# XHDZ-FZ-2E.net
KiCad netlist of a schematic drawn in EAGLE
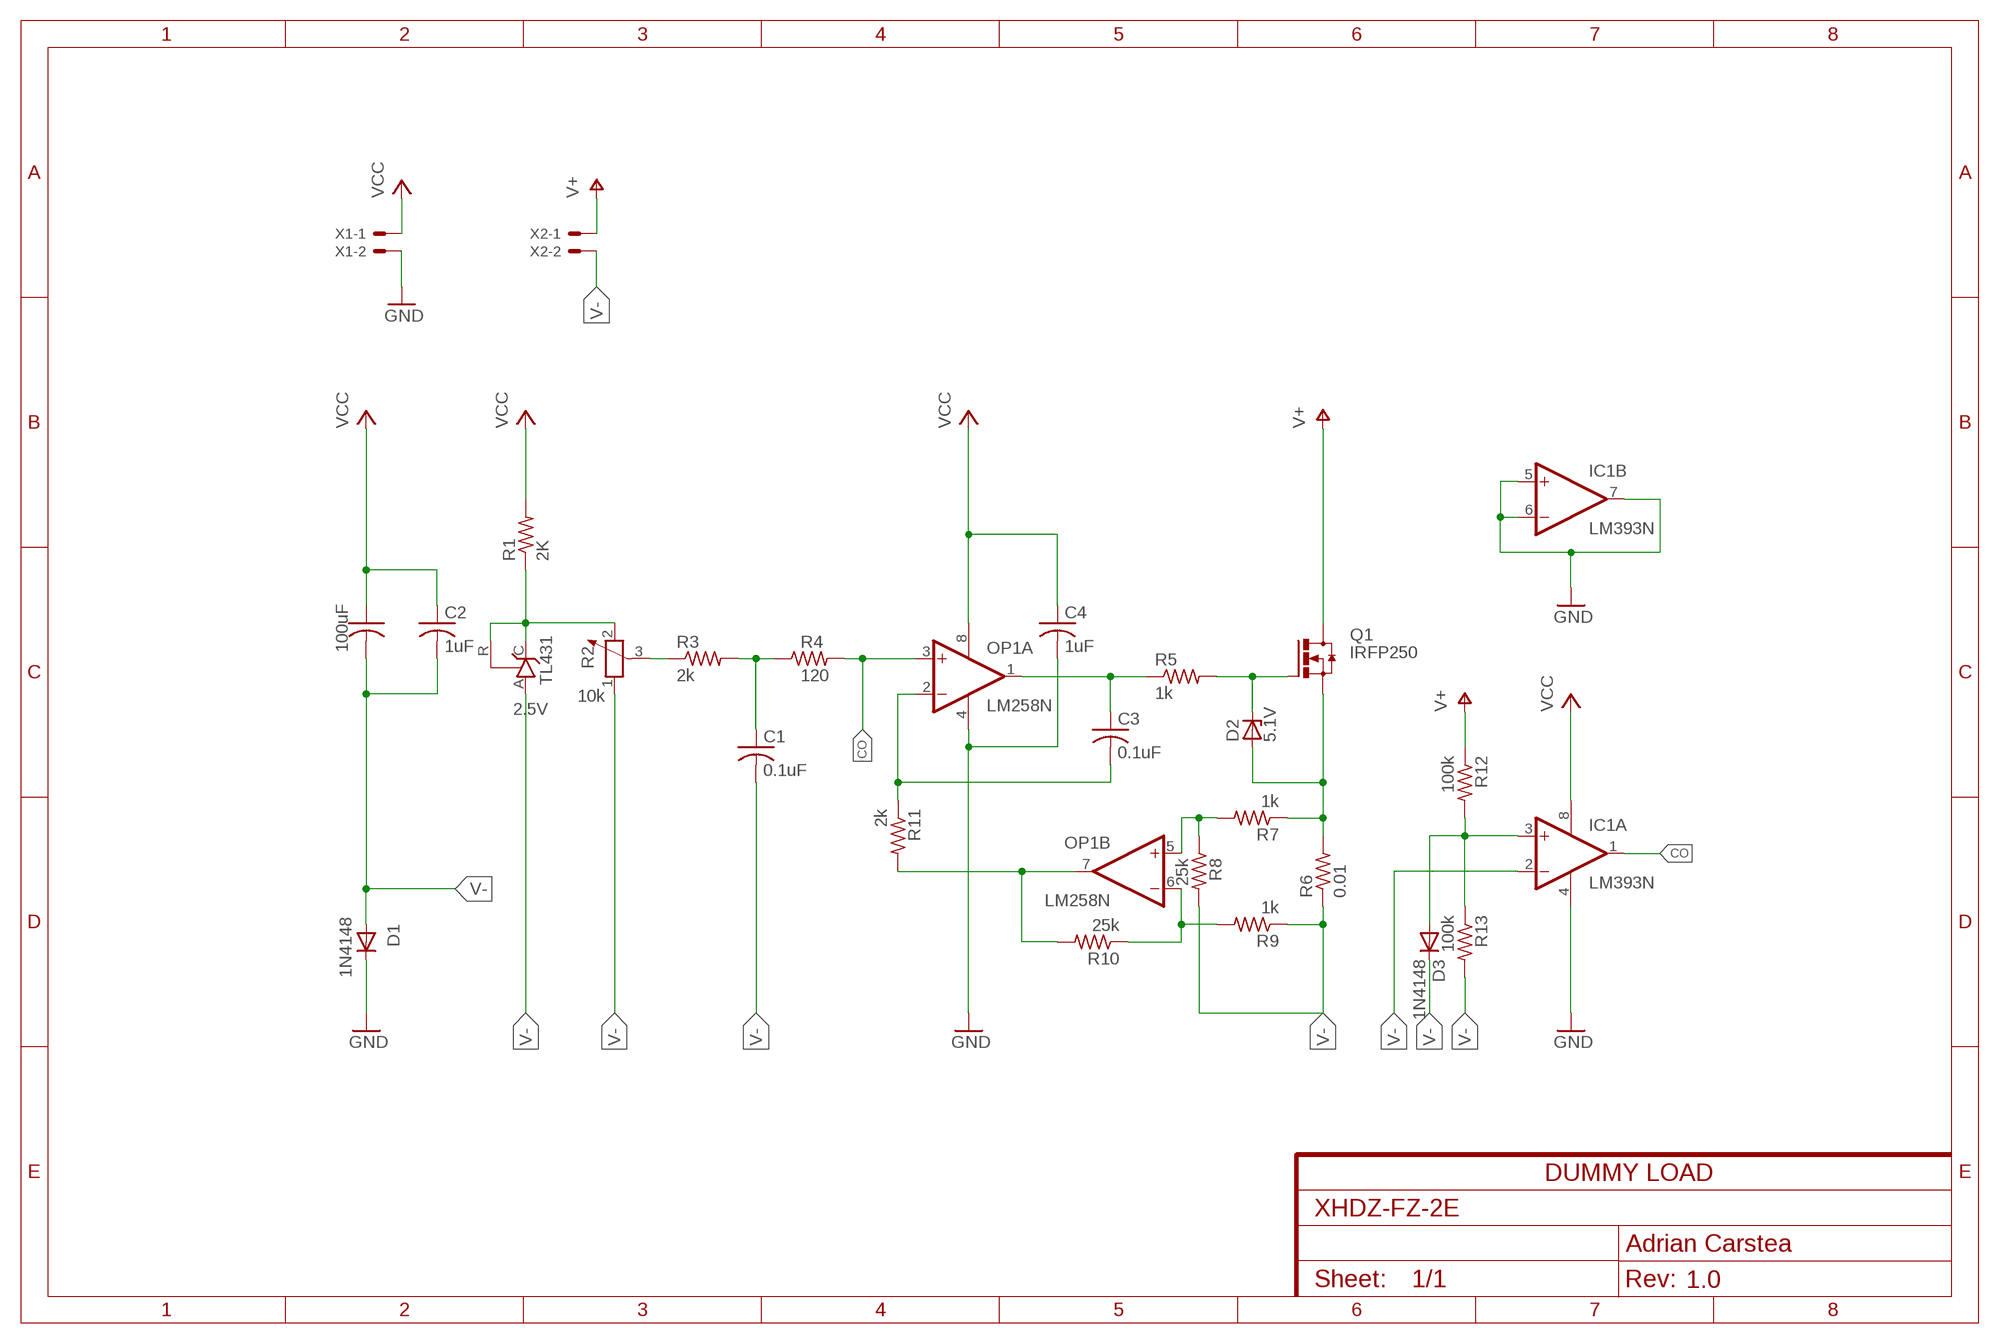
[diagram p0: schematic, sheet 1]

(export (version "E")
  (design (tool "Eeschema 10.0.6"))
  (components
    (comp (ref "25V")
      (value "100uF")
      (footprint "eagle-import:C025-024X044")
      (libsource (lib "eagle-import") (part "C-US025-024X044"))
    )
    (comp (ref "C1")
      (value "0.1uF")
      (footprint "eagle-import:C025-024X044")
      (libsource (lib "eagle-import") (part "C-US025-024X044"))
    )
    (comp (ref "C2")
      (value "1uF")
      (footprint "eagle-import:C025-024X044")
      (libsource (lib "eagle-import") (part "C-US025-024X044"))
    )
    (comp (ref "C3")
      (value "0.1uF")
      (footprint "eagle-import:C025-024X044")
      (libsource (lib "eagle-import") (part "C-US025-024X044"))
    )
    (comp (ref "C4")
      (value "1uF")
      (footprint "eagle-import:C025-024X044")
      (libsource (lib "eagle-import") (part "C-US025-024X044"))
    )
    (comp (ref "D1")
      (value "1N4148")
      (footprint "eagle-import:DO35-7")
      (libsource (lib "eagle-import") (part "1N4148DO35-7"))
    )
    (comp (ref "D2")
      (value "5.1V")
      (footprint "eagle-import:C1702-15")
      (libsource (lib "eagle-import") (part "ZENER-DIODEC1702-15"))
    )
    (comp (ref "D3")
      (value "1N4148")
      (footprint "eagle-import:DO35-7")
      (libsource (lib "eagle-import") (part "1N4148DO35-7"))
    )
    (comp (ref "IC1")
      (value "LM393N")
      (footprint "eagle-import:DIL08")
      (libsource (lib "eagle-import") (part "LM393N"))
    )
    (comp (ref "OP1")
      (value "LM258N")
      (footprint "eagle-import:DIL08")
      (libsource (lib "eagle-import") (part "LM358N"))
    )
    (comp (ref "Q1")
      (value "IRFP250")
      (footprint "eagle-import:TO-247AD-V")
      (libsource (lib "eagle-import") (part "IRFP250"))
    )
    (comp (ref "R1")
      (value "2K")
      (footprint "eagle-import:0207_5V")
      (libsource (lib "eagle-import") (part "R-US_0207/5V"))
    )
    (comp (ref "R2")
      (value "10k")
      (footprint "eagle-import:PT-10")
      (libsource (lib "eagle-import") (part "POTENTIOMETER_PT-10"))
    )
    (comp (ref "R3")
      (value "2k")
      (footprint "eagle-import:0207_5V")
      (libsource (lib "eagle-import") (part "R-US_0207/5V"))
    )
    (comp (ref "R4")
      (value "120")
      (footprint "eagle-import:0207_5V")
      (libsource (lib "eagle-import") (part "R-US_0207/5V"))
    )
    (comp (ref "R5")
      (value "1k")
      (footprint "eagle-import:0207_5V")
      (libsource (lib "eagle-import") (part "R-US_0207/5V"))
    )
    (comp (ref "R6")
      (value "0.01")
      (footprint "eagle-import:0207_5V")
      (libsource (lib "eagle-import") (part "R-US_0207/5V"))
    )
    (comp (ref "R7")
      (value "1k")
      (footprint "eagle-import:0207_5V")
      (libsource (lib "eagle-import") (part "R-US_0207/5V"))
    )
    (comp (ref "R8")
      (value "25k")
      (footprint "eagle-import:0207_5V")
      (libsource (lib "eagle-import") (part "R-US_0207/5V"))
    )
    (comp (ref "R9")
      (value "1k")
      (footprint "eagle-import:0207_5V")
      (libsource (lib "eagle-import") (part "R-US_0207/5V"))
    )
    (comp (ref "R10")
      (value "25k")
      (footprint "eagle-import:0207_5V")
      (libsource (lib "eagle-import") (part "R-US_0207/5V"))
    )
    (comp (ref "R11")
      (value "2k")
      (footprint "eagle-import:0207_5V")
      (libsource (lib "eagle-import") (part "R-US_0207/5V"))
    )
    (comp (ref "R12")
      (value "100k")
      (footprint "eagle-import:0207_5V")
      (libsource (lib "eagle-import") (part "R-US_0207/5V"))
    )
    (comp (ref "R13")
      (value "100k")
      (footprint "eagle-import:0207_5V")
      (libsource (lib "eagle-import") (part "R-US_0207/5V"))
    )
    (comp (ref "TL431")
      (value "2.5V")
      (footprint "eagle-import:TO92-CLP")
      (libsource (lib "eagle-import") (part "TL431CLP"))
    )
    (comp (ref "X1")
      (value "22-23-2021")
      (footprint "eagle-import:22-23-2021")
      (fields (field (name "MF") "MOLEX"))
      (libsource (lib "eagle-import") (part "22-23-2021"))
    )
    (comp (ref "X2")
      (value "22-23-2021")
      (footprint "eagle-import:22-23-2021")
      (fields (field (name "MF") "MOLEX"))
      (libsource (lib "eagle-import") (part "22-23-2021"))
    )
  )
  (nets
    (net (code "1") (name "CO") (class "Default")
      (node (ref "IC1") (pin "1") (pinfunction "OUT_1") (pintype "output"))
      (node (ref "OP1") (pin "3") (pinfunction "+IN_3") (pintype "input"))
      (node (ref "R4") (pin "2") (pinfunction "2_2") (pintype "passive"))
    )
    (net (code "2") (name "GND") (class "Default")
      (node (ref "C4") (pin "2") (pinfunction "2_2") (pintype "passive"))
      (node (ref "D1") (pin "C") (pinfunction "C_C") (pintype "passive"))
      (node (ref "IC1") (pin "4") (pinfunction "V-_4") (pintype "power_in"))
      (node (ref "IC1") (pin "5") (pinfunction "+IN_5") (pintype "input"))
      (node (ref "IC1") (pin "6") (pinfunction "-IN_6") (pintype "input"))
      (node (ref "IC1") (pin "7") (pinfunction "OUT_7") (pintype "output"))
      (node (ref "OP1") (pin "4") (pinfunction "V-_4") (pintype "power_in"))
      (node (ref "X1") (pin "2") (pinfunction "S_2") (pintype "passive"))
    )
    (net (code "3") (name "Net-(C1-Pad1)") (class "Default")
      (node (ref "C1") (pin "1") (pinfunction "1_1") (pintype "passive"))
      (node (ref "R3") (pin "2") (pinfunction "2_2") (pintype "passive"))
      (node (ref "R4") (pin "1") (pinfunction "1_1") (pintype "passive"))
    )
    (net (code "4") (name "Net-(D2-PadA)") (class "Default")
      (node (ref "D2") (pin "A") (pinfunction "A_A") (pintype "passive"))
      (node (ref "Q1") (pin "S") (pinfunction "S_S") (pintype "passive"))
      (node (ref "R6") (pin "2") (pinfunction "2_2") (pintype "passive"))
      (node (ref "R7") (pin "1") (pinfunction "1_1") (pintype "passive"))
    )
    (net (code "5") (name "Net-(D2-PadC)") (class "Default")
      (node (ref "D2") (pin "C") (pinfunction "C_C") (pintype "passive"))
      (node (ref "Q1") (pin "G") (pinfunction "G_G") (pintype "passive"))
      (node (ref "R5") (pin "2") (pinfunction "2_2") (pintype "passive"))
    )
    (net (code "6") (name "Net-(IC1A-+IN)") (class "Default")
      (node (ref "D3") (pin "A") (pinfunction "A_A") (pintype "passive"))
      (node (ref "IC1") (pin "3") (pinfunction "+IN_3") (pintype "input"))
      (node (ref "R12") (pin "2") (pinfunction "2_2") (pintype "passive"))
      (node (ref "R13") (pin "1") (pinfunction "1_1") (pintype "passive"))
    )
    (net (code "7") (name "Net-(OP1A--IN)") (class "Default")
      (node (ref "C3") (pin "2") (pinfunction "2_2") (pintype "passive"))
      (node (ref "OP1") (pin "2") (pinfunction "-IN_2") (pintype "input"))
      (node (ref "R11") (pin "1") (pinfunction "1_1") (pintype "passive"))
    )
    (net (code "8") (name "Net-(OP1A-OUT)") (class "Default")
      (node (ref "C3") (pin "1") (pinfunction "1_1") (pintype "passive"))
      (node (ref "OP1") (pin "1") (pinfunction "OUT_1") (pintype "output"))
      (node (ref "R5") (pin "1") (pinfunction "1_1") (pintype "passive"))
    )
    (net (code "9") (name "Net-(OP1B-+IN)") (class "Default")
      (node (ref "OP1") (pin "5") (pinfunction "+IN_5") (pintype "input"))
      (node (ref "R7") (pin "2") (pinfunction "2_2") (pintype "passive"))
      (node (ref "R8") (pin "1") (pinfunction "1_1") (pintype "passive"))
    )
    (net (code "10") (name "Net-(OP1B--IN)") (class "Default")
      (node (ref "OP1") (pin "6") (pinfunction "-IN_6") (pintype "input"))
      (node (ref "R10") (pin "1") (pinfunction "1_1") (pintype "passive"))
      (node (ref "R9") (pin "2") (pinfunction "2_2") (pintype "passive"))
    )
    (net (code "11") (name "Net-(OP1B-OUT)") (class "Default")
      (node (ref "OP1") (pin "7") (pinfunction "OUT_7") (pintype "output"))
      (node (ref "R10") (pin "2") (pinfunction "2_2") (pintype "passive"))
      (node (ref "R11") (pin "2") (pinfunction "2_2") (pintype "passive"))
    )
    (net (code "12") (name "Net-(R1-Pad1)") (class "Default")
      (node (ref "R1") (pin "1") (pinfunction "1_1") (pintype "passive"))
      (node (ref "R2") (pin "2") (pinfunction "2_2") (pintype "passive"))
      (node (ref "TL431") (pin "C") (pinfunction "C_C") (pintype "passive"))
      (node (ref "TL431") (pin "R") (pinfunction "R_R") (pintype "passive"))
    )
    (net (code "13") (name "Net-(R2-Pad3)") (class "Default")
      (node (ref "R2") (pin "3") (pinfunction "3_3") (pintype "passive"))
      (node (ref "R3") (pin "1") (pinfunction "1_1") (pintype "passive"))
    )
    (net (code "14") (name "V+") (class "Default")
      (node (ref "Q1") (pin "D") (pinfunction "D_D") (pintype "passive"))
      (node (ref "R12") (pin "1") (pinfunction "1_1") (pintype "passive"))
      (node (ref "X2") (pin "1") (pinfunction "S_1") (pintype "passive"))
    )
    (net (code "15") (name "V-") (class "Default")
      (node (ref "25V") (pin "2") (pinfunction "2_2") (pintype "passive"))
      (node (ref "C1") (pin "2") (pinfunction "2_2") (pintype "passive"))
      (node (ref "C2") (pin "2") (pinfunction "2_2") (pintype "passive"))
      (node (ref "D1") (pin "A") (pinfunction "A_A") (pintype "passive"))
      (node (ref "D3") (pin "C") (pinfunction "C_C") (pintype "passive"))
      (node (ref "IC1") (pin "2") (pinfunction "-IN_2") (pintype "input"))
      (node (ref "R13") (pin "2") (pinfunction "2_2") (pintype "passive"))
      (node (ref "R2") (pin "1") (pinfunction "1_1") (pintype "passive"))
      (node (ref "R6") (pin "1") (pinfunction "1_1") (pintype "passive"))
      (node (ref "R8") (pin "2") (pinfunction "2_2") (pintype "passive"))
      (node (ref "R9") (pin "1") (pinfunction "1_1") (pintype "passive"))
      (node (ref "TL431") (pin "A") (pinfunction "A_A") (pintype "passive"))
      (node (ref "X2") (pin "2") (pinfunction "S_2") (pintype "passive"))
    )
    (net (code "16") (name "VCC") (class "Default")
      (node (ref "25V") (pin "1") (pinfunction "1_1") (pintype "passive"))
      (node (ref "C2") (pin "1") (pinfunction "1_1") (pintype "passive"))
      (node (ref "C4") (pin "1") (pinfunction "1_1") (pintype "passive"))
      (node (ref "IC1") (pin "8") (pinfunction "V+_8") (pintype "power_in"))
      (node (ref "OP1") (pin "8") (pinfunction "V+_8") (pintype "power_in"))
      (node (ref "R1") (pin "2") (pinfunction "2_2") (pintype "passive"))
      (node (ref "X1") (pin "1") (pinfunction "S_1") (pintype "passive"))
    )
  )
)
